# PiZeroAudioI2S.net
KiCad netlist of a schematic drawn in EAGLE
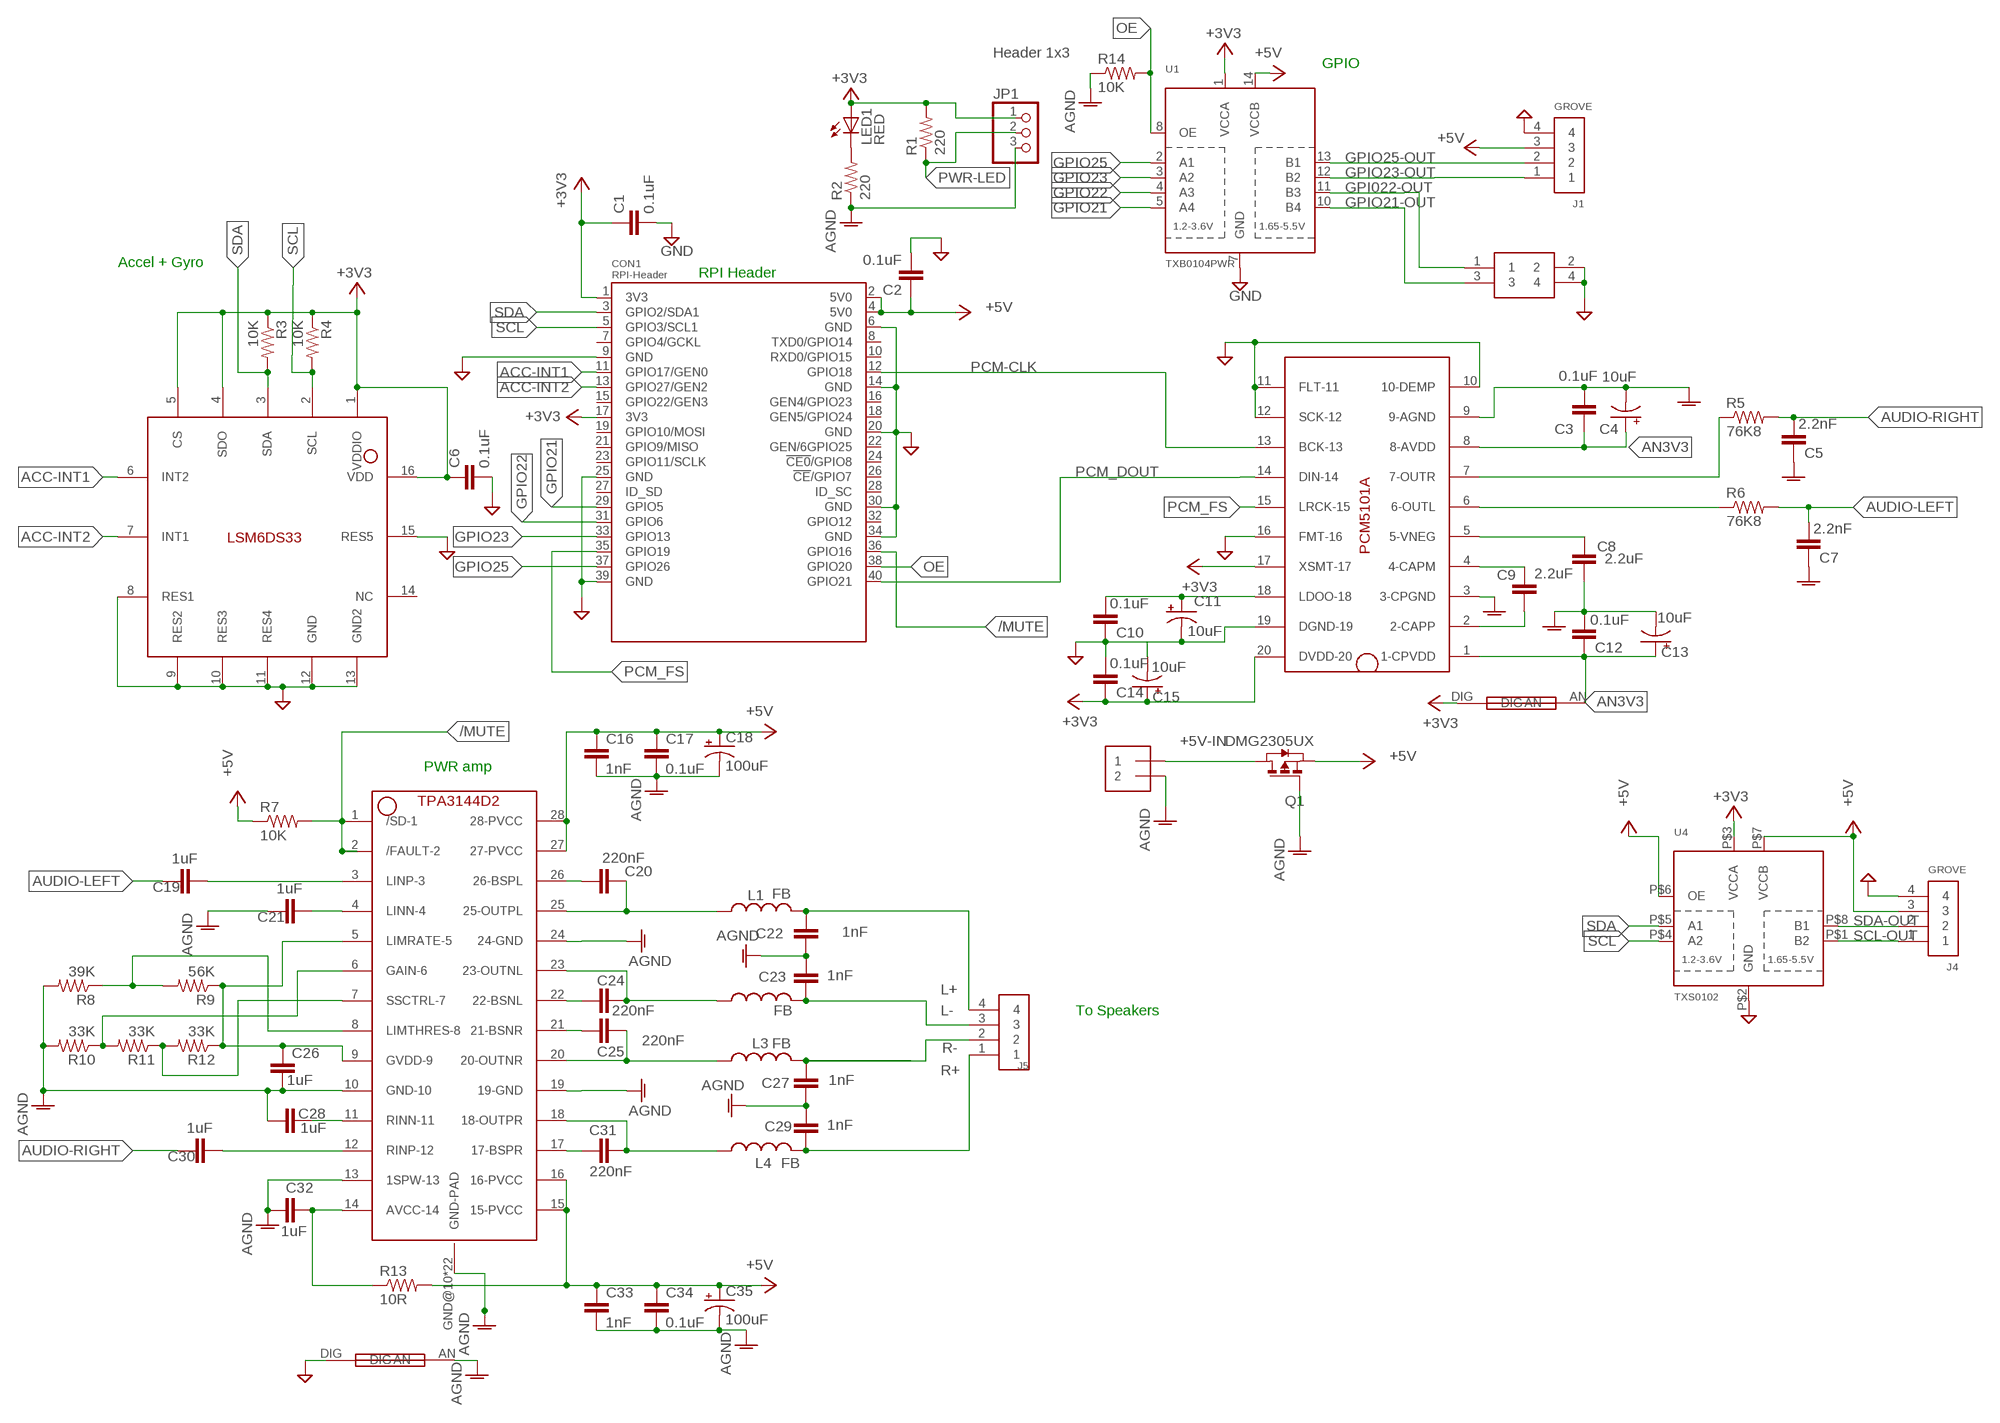
[diagram p0: schematic, sheet 1]

(export (version "E")
  (design (tool "Eeschema 10.0.6"))
  (components
    (comp (ref "C1")
      (value "0.1uF")
      (footprint "eagle-import:C0603")
      (libsource (lib "eagle-import") (part "C-EUC0603"))
    )
    (comp (ref "C2")
      (value "0.1uF")
      (footprint "eagle-import:C0603")
      (libsource (lib "eagle-import") (part "C-EUC0603"))
    )
    (comp (ref "C3")
      (value "0.1uF")
      (footprint "eagle-import:C0603")
      (libsource (lib "eagle-import") (part "C-EUC0603"))
    )
    (comp (ref "C4")
      (value "10uF")
      (footprint "eagle-import:EIA3216")
      (fields (field (name "MF") "AVX") (field (name "MPN") "F931C106MAA"))
      (libsource (lib "eagle-import") (part "CAP-POLARISED1206-POLAR"))
    )
    (comp (ref "C5")
      (value "2.2nF")
      (footprint "eagle-import:C0603")
      (fields (field (name "MF") "WALSIN") (field (name "MPN") "0603B222K500CT"))
      (libsource (lib "eagle-import") (part "C-EUC0603"))
    )
    (comp (ref "C6")
      (value "0.1uF")
      (footprint "eagle-import:C0603")
      (libsource (lib "eagle-import") (part "C-EUC0603"))
    )
    (comp (ref "C7")
      (value "2.2nF")
      (footprint "eagle-import:C0603")
      (fields (field (name "MF") "WALSIN") (field (name "MPN") "0603B222K500CT"))
      (libsource (lib "eagle-import") (part "C-EUC0603"))
    )
    (comp (ref "C8")
      (value "2.2uF")
      (footprint "eagle-import:C0603")
      (fields (field (name "MF") "KEMET") (field (name "MPN") "C0603C225K8PACTU"))
      (libsource (lib "eagle-import") (part "C-EUC0603"))
    )
    (comp (ref "C9")
      (value "2.2uF")
      (footprint "eagle-import:C0603")
      (fields (field (name "MF") "KEMET") (field (name "MPN") "C0603C225K8PACTU"))
      (libsource (lib "eagle-import") (part "C-EUC0603"))
    )
    (comp (ref "C10")
      (value "0.1uF")
      (footprint "eagle-import:C0603")
      (libsource (lib "eagle-import") (part "C-EUC0603"))
    )
    (comp (ref "C11")
      (value "10uF")
      (footprint "eagle-import:EIA3216")
      (fields (field (name "MF") "AVX") (field (name "MPN") "F931C106MAA"))
      (libsource (lib "eagle-import") (part "CAP-POLARISED1206-POLAR"))
    )
    (comp (ref "C12")
      (value "0.1uF")
      (footprint "eagle-import:C0603")
      (libsource (lib "eagle-import") (part "C-EUC0603"))
    )
    (comp (ref "C13")
      (value "10uF")
      (footprint "eagle-import:EIA3216")
      (fields (field (name "MF") "AVX") (field (name "MPN") "F931C106MAA"))
      (libsource (lib "eagle-import") (part "CAP-POLARISED1206-POLAR"))
    )
    (comp (ref "C14")
      (value "0.1uF")
      (footprint "eagle-import:C0603")
      (libsource (lib "eagle-import") (part "C-EUC0603"))
    )
    (comp (ref "C15")
      (value "10uF")
      (footprint "eagle-import:EIA3216")
      (fields (field (name "MF") "AVX") (field (name "MPN") "F931C106MAA"))
      (libsource (lib "eagle-import") (part "CAP-POLARISED1206-POLAR"))
    )
    (comp (ref "C16")
      (value "1nF")
      (footprint "eagle-import:C0603")
      (fields (field (name "MF") "AVX") (field (name "MPN") "06035C102KAT2A"))
      (libsource (lib "eagle-import") (part "C-EUC0603"))
    )
    (comp (ref "C17")
      (value "0.1uF")
      (footprint "eagle-import:C0603")
      (libsource (lib "eagle-import") (part "C-EUC0603"))
    )
    (comp (ref "C18")
      (value "100uF")
      (footprint "eagle-import:EIA3216")
      (fields (field (name "MF") "AVX") (field (name "MPN") "TLJA107M010R1400"))
      (libsource (lib "eagle-import") (part "CAP-POLARISED1206-POLAR"))
    )
    (comp (ref "C19")
      (value "1uF")
      (footprint "eagle-import:C0603")
      (libsource (lib "eagle-import") (part "C-EUC0603"))
    )
    (comp (ref "C20")
      (value "220nF")
      (footprint "eagle-import:C0603")
      (fields (field (name "MF") "TAIYO YUDEN") (field (name "MPN") "EMK107B7224KA-T"))
      (libsource (lib "eagle-import") (part "C-EUC0603"))
    )
    (comp (ref "C21")
      (value "1uF")
      (footprint "eagle-import:C0603")
      (libsource (lib "eagle-import") (part "C-EUC0603"))
    )
    (comp (ref "C22")
      (value "1nF")
      (footprint "eagle-import:C0603")
      (fields (field (name "MF") "AVX") (field (name "MPN") "06035C102KAT2A"))
      (libsource (lib "eagle-import") (part "C-EUC0603"))
    )
    (comp (ref "C23")
      (value "1nF")
      (footprint "eagle-import:C0603")
      (fields (field (name "MF") "AVX") (field (name "MPN") "06035C102KAT2A"))
      (libsource (lib "eagle-import") (part "C-EUC0603"))
    )
    (comp (ref "C24")
      (value "220nF")
      (footprint "eagle-import:C0603")
      (fields (field (name "MF") "TAIYO YUDEN") (field (name "MPN") "EMK107B7224KA-T"))
      (libsource (lib "eagle-import") (part "C-EUC0603"))
    )
    (comp (ref "C25")
      (value "220nF")
      (footprint "eagle-import:C0603")
      (fields (field (name "MF") "TAIYO YUDEN") (field (name "MPN") "EMK107B7224KA-T"))
      (libsource (lib "eagle-import") (part "C-EUC0603"))
    )
    (comp (ref "C26")
      (value "1uF")
      (footprint "eagle-import:C0603")
      (libsource (lib "eagle-import") (part "C-EUC0603"))
    )
    (comp (ref "C27")
      (value "1nF")
      (footprint "eagle-import:C0603")
      (fields (field (name "MF") "AVX") (field (name "MPN") "06035C102KAT2A"))
      (libsource (lib "eagle-import") (part "C-EUC0603"))
    )
    (comp (ref "C28")
      (value "1uF")
      (footprint "eagle-import:C0603")
      (libsource (lib "eagle-import") (part "C-EUC0603"))
    )
    (comp (ref "C29")
      (value "1nF")
      (footprint "eagle-import:C0603")
      (fields (field (name "MF") "AVX") (field (name "MPN") "06035C102KAT2A"))
      (libsource (lib "eagle-import") (part "C-EUC0603"))
    )
    (comp (ref "C30")
      (value "1uF")
      (footprint "eagle-import:C0603")
      (libsource (lib "eagle-import") (part "C-EUC0603"))
    )
    (comp (ref "C31")
      (value "220nF")
      (footprint "eagle-import:C0603")
      (fields (field (name "MF") "TAIYO YUDEN") (field (name "MPN") "EMK107B7224KA-T"))
      (libsource (lib "eagle-import") (part "C-EUC0603"))
    )
    (comp (ref "C32")
      (value "1uF")
      (footprint "eagle-import:C0603")
      (libsource (lib "eagle-import") (part "C-EUC0603"))
    )
    (comp (ref "C33")
      (value "1nF")
      (footprint "eagle-import:C0603")
      (fields (field (name "MF") "AVX") (field (name "MPN") "06035C102KAT2A"))
      (libsource (lib "eagle-import") (part "C-EUC0603"))
    )
    (comp (ref "C34")
      (value "0.1uF")
      (footprint "eagle-import:C0603")
      (libsource (lib "eagle-import") (part "C-EUC0603"))
    )
    (comp (ref "C35")
      (value "100uF")
      (footprint "eagle-import:EIA3216")
      (fields (field (name "MF") "AVX") (field (name "MPN") "TLJA107M010R1400"))
      (libsource (lib "eagle-import") (part "CAP-POLARISED1206-POLAR"))
    )
    (comp (ref "CON1")
      (value "RPI-Header")
      (footprint "eagle-import:RASPBERRYPI_BASTELSTUBE_V13_RASPI_BOARD_B+_FULL")
      (libsource (lib "eagle-import") (part "RPI-ZERO"))
    )
    (comp (ref "J1")
      (value "GROVE")
      (footprint "eagle-import:JST-PH4")
      (libsource (lib "eagle-import") (part "GROVE"))
    )
    (comp (ref "J2")
      (value "2X2HEADER")
      (footprint "eagle-import:2X2")
      (libsource (lib "eagle-import") (part "2X2HEADER"))
    )
    (comp (ref "J3")
      (value "2X1-LOCKING")
      (footprint "eagle-import:22-23-2021")
      (fields (field (name "MF") "MOLEX") (field (name "MPN") "22-23-2021"))
      (libsource (lib "eagle-import") (part "2X1-LOCKING"))
    )
    (comp (ref "J4")
      (value "GROVE")
      (footprint "eagle-import:JST-PH4")
      (libsource (lib "eagle-import") (part "GROVE"))
    )
    (comp (ref "J5")
      (value "4X1-LOCKING")
      (footprint "eagle-import:22-23-2041")
      (fields (field (name "MF") "MOLEX") (field (name "MPN") "22-23-2041"))
      (libsource (lib "eagle-import") (part "4X1-LOCKING"))
    )
    (comp (ref "JP1")
      (value "Header 1x3")
      (footprint "eagle-import:1X03")
      (libsource (lib "eagle-import") (part "PINHD-1X3"))
    )
    (comp (ref "L1")
      (value "FB")
      (footprint "eagle-import:L0806")
      (libsource (lib "eagle-import") (part "NFZ2MSML0806"))
    )
    (comp (ref "L2")
      (value "FB")
      (footprint "eagle-import:L0806")
      (libsource (lib "eagle-import") (part "NFZ2MSML0806"))
    )
    (comp (ref "L3")
      (value "FB")
      (footprint "eagle-import:L0806")
      (libsource (lib "eagle-import") (part "NFZ2MSML0806"))
    )
    (comp (ref "L4")
      (value "FB")
      (footprint "eagle-import:L0806")
      (libsource (lib "eagle-import") (part "NFZ2MSML0806"))
    )
    (comp (ref "LED1")
      (value "RED")
      (footprint "eagle-import:CHIP-LED0805")
      (libsource (lib "eagle-import") (part "LEDCHIP-LED0805"))
    )
    (comp (ref "Q1")
      (value "DMG2305UX")
      (footprint "eagle-import:SOT23")
      (fields (field (name "MF") "DIODES INC.") (field (name "MPN") "DMG2305UX-7"))
      (libsource (lib "eagle-import") (part "DMG2305UX"))
    )
    (comp (ref "R1")
      (value "220")
      (footprint "eagle-import:R0603")
      (libsource (lib "eagle-import") (part "R-US_R0603"))
    )
    (comp (ref "R2")
      (value "220")
      (footprint "eagle-import:R0603")
      (libsource (lib "eagle-import") (part "R-US_R0603"))
    )
    (comp (ref "R3")
      (value "10K")
      (footprint "eagle-import:R0603")
      (fields (field (name "MF") "YAGEO") (field (name "MPN") "RC0603FR-0710KL"))
      (libsource (lib "eagle-import") (part "R-US_R0603"))
    )
    (comp (ref "R4")
      (value "10K")
      (footprint "eagle-import:R0603")
      (fields (field (name "MF") "YAGEO") (field (name "MPN") "RC0603FR-0710KL"))
      (libsource (lib "eagle-import") (part "R-US_R0603"))
    )
    (comp (ref "R5")
      (value "76K8")
      (footprint "eagle-import:R0603")
      (fields (field (name "MF") "PANASONIC ELECTRONIC COMPONENTS") (field (name "MPN") "RMCF0603FT76K8"))
      (libsource (lib "eagle-import") (part "R-US_R0603"))
    )
    (comp (ref "R6")
      (value "76K8")
      (footprint "eagle-import:R0603")
      (fields (field (name "MF") "PANASONIC ELECTRONIC COMPONENTS") (field (name "MPN") "RMCF0603FT76K8"))
      (libsource (lib "eagle-import") (part "R-US_R0603"))
    )
    (comp (ref "R7")
      (value "10K")
      (footprint "eagle-import:R0603")
      (fields (field (name "MF") "YAGEO") (field (name "MPN") "RC0603FR-0710KL"))
      (libsource (lib "eagle-import") (part "R-US_R0603"))
    )
    (comp (ref "R8")
      (value "39K")
      (footprint "eagle-import:R0603")
      (fields (field (name "MF") "YAGEO") (field (name "MPN") "RC0603FR-0739KL"))
      (libsource (lib "eagle-import") (part "R-US_R0603"))
    )
    (comp (ref "R9")
      (value "56K")
      (footprint "eagle-import:R0603")
      (fields (field (name "MF") "VISHAY") (field (name "MPN") "CRCW060356K0FKEA."))
      (libsource (lib "eagle-import") (part "R-US_R0603"))
    )
    (comp (ref "R10")
      (value "33K")
      (footprint "eagle-import:R0603")
      (fields (field (name "MF") "MULTICOMP") (field (name "MPN") "MCMR06X3302FTL"))
      (libsource (lib "eagle-import") (part "R-US_R0603"))
    )
    (comp (ref "R11")
      (value "33K")
      (footprint "eagle-import:R0603")
      (fields (field (name "MF") "MULTICOMP") (field (name "MPN") "MCMR06X3302FTL"))
      (libsource (lib "eagle-import") (part "R-US_R0603"))
    )
    (comp (ref "R12")
      (value "33K")
      (footprint "eagle-import:R0603")
      (fields (field (name "MF") "MULTICOMP") (field (name "MPN") "MCMR06X3302FTL"))
      (libsource (lib "eagle-import") (part "R-US_R0603"))
    )
    (comp (ref "R13")
      (value "10R")
      (footprint "eagle-import:R0603")
      (libsource (lib "eagle-import") (part "R-US_R0603"))
    )
    (comp (ref "R14")
      (value "10K")
      (footprint "eagle-import:R0603")
      (fields (field (name "MF") "YAGEO") (field (name "MPN") "RC0603FR-0710KL"))
      (libsource (lib "eagle-import") (part "R-US_R0603"))
    )
    (comp (ref "SH1")
      (value "SHORT")
      (footprint "eagle-import:SHORT")
      (libsource (lib "eagle-import") (part "SHORT"))
    )
    (comp (ref "SH2")
      (value "SHORT")
      (footprint "eagle-import:SHORT")
      (libsource (lib "eagle-import") (part "SHORT"))
    )
    (comp (ref "U1")
      (value "TXB0104PWR")
      (footprint "eagle-import:TSSOP14")
      (fields (field (name "MF") "TEXAS INSTRUMENTS"))
      (libsource (lib "eagle-import") (part "TXB0104PWR"))
    )
    (comp (ref "U2")
      (value "LSM6DS33")
      (footprint "eagle-import:LGA-16-3X3")
      (fields (field (name "MF") "STMICROELECTRONICS") (field (name "MPN") "LSM6DS33TR"))
      (libsource (lib "eagle-import") (part "LSM6DS33LGA-16-3X3"))
    )
    (comp (ref "U3")
      (value "PCM5101A")
      (footprint "eagle-import:TSSOP20-0.65-6.5X4.4MM")
      (fields (field (name "MF") "TEXAS INSTRUMENTS") (field (name "MPN") "PCM5101AQPWRQ1"))
      (libsource (lib "eagle-import") (part "PCM5101A"))
    )
    (comp (ref "U4")
      (value "TXS0102")
      (footprint "eagle-import:VFSOP-8")
      (libsource (lib "eagle-import") (part "TXS0102"))
    )
    (comp (ref "U5")
      (value "TPA3144D2PWPR")
      (footprint "eagle-import:HTSSOP28")
      (libsource (lib "eagle-import") (part "TPA3144D2PWPR"))
    )
  )
  (nets
    (net (code "1") (name "+3V3") (class "Default")
      (node (ref "C1") (pin "1") (pinfunction "1_1") (pintype "passive"))
      (node (ref "C14") (pin "2") (pinfunction "2_2") (pintype "passive"))
      (node (ref "C15") (pin "+") (pinfunction "+_+") (pintype "passive"))
      (node (ref "C6") (pin "1") (pinfunction "1_1") (pintype "passive"))
      (node (ref "CON1") (pin "1") (pinfunction "3V3_1") (pintype "power_in"))
      (node (ref "CON1") (pin "17") (pinfunction "3V3_17") (pintype "power_in"))
      (node (ref "JP1") (pin "1") (pinfunction "1_1") (pintype "passive"))
      (node (ref "LED1") (pin "A") (pinfunction "A_A") (pintype "passive"))
      (node (ref "R1") (pin "2") (pinfunction "2_2") (pintype "passive"))
      (node (ref "R3") (pin "1") (pinfunction "1_1") (pintype "passive"))
      (node (ref "R4") (pin "1") (pinfunction "1_1") (pintype "passive"))
      (node (ref "SH1") (pin "DIG") (pinfunction "DIG_DIG") (pintype "bidirectional"))
      (node (ref "U1") (pin "1") (pinfunction "VCCA_1") (pintype "bidirectional"))
      (node (ref "U2") (pin "1") (pinfunction "VDDIO_1") (pintype "bidirectional"))
      (node (ref "U2") (pin "16") (pinfunction "VDD_16") (pintype "bidirectional"))
      (node (ref "U2") (pin "4") (pinfunction "SDO_4") (pintype "bidirectional"))
      (node (ref "U2") (pin "5") (pinfunction "CS_5") (pintype "bidirectional"))
      (node (ref "U3") (pin "17") (pinfunction "XSMT-17_17") (pintype "bidirectional"))
      (node (ref "U3") (pin "20") (pinfunction "DVDD-20_20") (pintype "bidirectional"))
      (node (ref "U4") (pin "P$3") (pinfunction "VCCA_P$3") (pintype "bidirectional"))
    )
    (net (code "2") (name "+5V") (class "Default")
      (node (ref "C16") (pin "1") (pinfunction "1_1") (pintype "passive"))
      (node (ref "C17") (pin "1") (pinfunction "1_1") (pintype "passive"))
      (node (ref "C18") (pin "+") (pinfunction "+_+") (pintype "passive"))
      (node (ref "C2") (pin "1") (pinfunction "1_1") (pintype "passive"))
      (node (ref "C33") (pin "1") (pinfunction "1_1") (pintype "passive"))
      (node (ref "C34") (pin "1") (pinfunction "1_1") (pintype "passive"))
      (node (ref "C35") (pin "+") (pinfunction "+_+") (pintype "passive"))
      (node (ref "CON1") (pin "2") (pinfunction "5V0_2") (pintype "power_in"))
      (node (ref "CON1") (pin "4") (pinfunction "5V0_4") (pintype "power_in"))
      (node (ref "J1") (pin "3") (pinfunction "3_3") (pintype "bidirectional"))
      (node (ref "J4") (pin "3") (pinfunction "3_3") (pintype "bidirectional"))
      (node (ref "Q1") (pin "S") (pinfunction "S_S") (pintype "passive"))
      (node (ref "R13") (pin "2") (pinfunction "2_2") (pintype "passive"))
      (node (ref "R7") (pin "1") (pinfunction "1_1") (pintype "passive"))
      (node (ref "U1") (pin "14") (pinfunction "VCCB_14") (pintype "bidirectional"))
      (node (ref "U4") (pin "P$6") (pinfunction "OE_P$6") (pintype "bidirectional"))
      (node (ref "U4") (pin "P$7") (pinfunction "VCCB_P$7") (pintype "bidirectional"))
      (node (ref "U5") (pin "15") (pinfunction "15-PVCC_15") (pintype "bidirectional"))
      (node (ref "U5") (pin "16") (pinfunction "16-PVCC_16") (pintype "bidirectional"))
      (node (ref "U5") (pin "27") (pinfunction "27-PVCC_27") (pintype "bidirectional"))
      (node (ref "U5") (pin "28") (pinfunction "28-PVCC_28") (pintype "bidirectional"))
    )
    (net (code "3") (name "/+5V-IN") (class "Default")
      (node (ref "J3") (pin "1") (pinfunction "1_1") (pintype "passive"))
      (node (ref "Q1") (pin "D") (pinfunction "D_D") (pintype "passive"))
    )
    (net (code "4") (name "/GPI022-OUT") (class "Default")
      (node (ref "J2") (pin "1") (pinfunction "1_1") (pintype "bidirectional"))
      (node (ref "U1") (pin "11") (pinfunction "B3_11") (pintype "bidirectional"))
    )
    (net (code "5") (name "/GPIO21-OUT") (class "Default")
      (node (ref "J2") (pin "3") (pinfunction "3_3") (pintype "bidirectional"))
      (node (ref "U1") (pin "10") (pinfunction "B4_10") (pintype "bidirectional"))
    )
    (net (code "6") (name "/GPIO23-OUT") (class "Default")
      (node (ref "J1") (pin "1") (pinfunction "1_1") (pintype "bidirectional"))
      (node (ref "U1") (pin "12") (pinfunction "B2_12") (pintype "bidirectional"))
    )
    (net (code "7") (name "/GPIO25-OUT") (class "Default")
      (node (ref "J1") (pin "2") (pinfunction "2_2") (pintype "bidirectional"))
      (node (ref "U1") (pin "13") (pinfunction "B1_13") (pintype "bidirectional"))
    )
    (net (code "8") (name "/L+") (class "Default")
      (node (ref "C22") (pin "1") (pinfunction "1_1") (pintype "passive"))
      (node (ref "J5") (pin "4") (pinfunction "4_4") (pintype "bidirectional"))
      (node (ref "L1") (pin "2") (pinfunction "2_2") (pintype "passive"))
    )
    (net (code "9") (name "/L-") (class "Default")
      (node (ref "C23") (pin "2") (pinfunction "2_2") (pintype "passive"))
      (node (ref "J5") (pin "3") (pinfunction "3_3") (pintype "bidirectional"))
      (node (ref "L2") (pin "2") (pinfunction "2_2") (pintype "passive"))
    )
    (net (code "10") (name "/PCM-CLK") (class "Default")
      (node (ref "CON1") (pin "12") (pinfunction "GPIO18_12") (pintype "bidirectional"))
      (node (ref "U3") (pin "13") (pinfunction "BCK-13_13") (pintype "bidirectional"))
    )
    (net (code "11") (name "/PCM_DOUT") (class "Default")
      (node (ref "CON1") (pin "40") (pinfunction "GPIO21_40") (pintype "bidirectional"))
      (node (ref "U3") (pin "14") (pinfunction "DIN-14_14") (pintype "bidirectional"))
    )
    (net (code "12") (name "/R+") (class "Default")
      (node (ref "C29") (pin "2") (pinfunction "2_2") (pintype "passive"))
      (node (ref "J5") (pin "1") (pinfunction "1_1") (pintype "bidirectional"))
      (node (ref "L4") (pin "2") (pinfunction "2_2") (pintype "passive"))
    )
    (net (code "13") (name "/R-") (class "Default")
      (node (ref "C27") (pin "1") (pinfunction "1_1") (pintype "passive"))
      (node (ref "J5") (pin "2") (pinfunction "2_2") (pintype "bidirectional"))
      (node (ref "L3") (pin "2") (pinfunction "2_2") (pintype "passive"))
    )
    (net (code "14") (name "/SCL-OUT") (class "Default")
      (node (ref "J4") (pin "1") (pinfunction "1_1") (pintype "bidirectional"))
      (node (ref "U4") (pin "P$1") (pinfunction "B2_P$1") (pintype "bidirectional"))
    )
    (net (code "15") (name "/SDA-OUT") (class "Default")
      (node (ref "J4") (pin "2") (pinfunction "2_2") (pintype "bidirectional"))
      (node (ref "U4") (pin "P$8") (pinfunction "B1_P$8") (pintype "bidirectional"))
    )
    (net (code "16") (name "ACC-INT1") (class "Default")
      (node (ref "CON1") (pin "11") (pinfunction "GPIO17/GEN0_11") (pintype "bidirectional"))
      (node (ref "U2") (pin "6") (pinfunction "INT2_6") (pintype "bidirectional"))
    )
    (net (code "17") (name "ACC-INT2") (class "Default")
      (node (ref "CON1") (pin "13") (pinfunction "GPIO27/GEN2_13") (pintype "bidirectional"))
      (node (ref "U2") (pin "7") (pinfunction "INT1_7") (pintype "bidirectional"))
    )
    (net (code "18") (name "AGND") (class "Default")
      (node (ref "C12") (pin "1") (pinfunction "1_1") (pintype "passive"))
      (node (ref "C13") (pin "-") (pinfunction "-_-") (pintype "passive"))
      (node (ref "C16") (pin "2") (pinfunction "2_2") (pintype "passive"))
      (node (ref "C17") (pin "2") (pinfunction "2_2") (pintype "passive"))
      (node (ref "C18") (pin "-") (pinfunction "-_-") (pintype "passive"))
      (node (ref "C21") (pin "2") (pinfunction "2_2") (pintype "passive"))
      (node (ref "C22") (pin "2") (pinfunction "2_2") (pintype "passive"))
      (node (ref "C23") (pin "1") (pinfunction "1_1") (pintype "passive"))
      (node (ref "C26") (pin "2") (pinfunction "2_2") (pintype "passive"))
      (node (ref "C27") (pin "2") (pinfunction "2_2") (pintype "passive"))
      (node (ref "C28") (pin "2") (pinfunction "2_2") (pintype "passive"))
      (node (ref "C29") (pin "1") (pinfunction "1_1") (pintype "passive"))
      (node (ref "C3") (pin "1") (pinfunction "1_1") (pintype "passive"))
      (node (ref "C32") (pin "2") (pinfunction "2_2") (pintype "passive"))
      (node (ref "C33") (pin "2") (pinfunction "2_2") (pintype "passive"))
      (node (ref "C34") (pin "2") (pinfunction "2_2") (pintype "passive"))
      (node (ref "C35") (pin "-") (pinfunction "-_-") (pintype "passive"))
      (node (ref "C4") (pin "-") (pinfunction "-_-") (pintype "passive"))
      (node (ref "C5") (pin "2") (pinfunction "2_2") (pintype "passive"))
      (node (ref "C7") (pin "2") (pinfunction "2_2") (pintype "passive"))
      (node (ref "C8") (pin "2") (pinfunction "2_2") (pintype "passive"))
      (node (ref "J3") (pin "2") (pinfunction "2_2") (pintype "passive"))
      (node (ref "JP1") (pin "3") (pinfunction "3_3") (pintype "passive"))
      (node (ref "Q1") (pin "G") (pinfunction "G_G") (pintype "passive"))
      (node (ref "R10") (pin "2") (pinfunction "2_2") (pintype "passive"))
      (node (ref "R14") (pin "1") (pinfunction "1_1") (pintype "passive"))
      (node (ref "R2") (pin "1") (pinfunction "1_1") (pintype "passive"))
      (node (ref "R8") (pin "2") (pinfunction "2_2") (pintype "passive"))
      (node (ref "SH2") (pin "AN") (pinfunction "AN_AN") (pintype "bidirectional"))
      (node (ref "U3") (pin "3") (pinfunction "3-CPGND_3") (pintype "bidirectional"))
      (node (ref "U3") (pin "9") (pinfunction "9-AGND_9") (pintype "bidirectional"))
      (node (ref "U5") (pin "10") (pinfunction "GND-10_10") (pintype "bidirectional"))
      (node (ref "U5") (pin "13") (pinfunction "1SPW-13_13") (pintype "bidirectional"))
      (node (ref "U5") (pin "19") (pinfunction "19-GND_19") (pintype "bidirectional"))
      (node (ref "U5") (pin "24") (pinfunction "24-GND_24") (pintype "bidirectional"))
      (node (ref "U5") (pin "GND@10") (pinfunction "GND-PAD_GND@10") (pintype "bidirectional"))
      (node (ref "U5") (pin "GND@11") (pinfunction "GND-PAD_GND@11") (pintype "bidirectional"))
      (node (ref "U5") (pin "GND@12") (pinfunction "GND-PAD_GND@12") (pintype "bidirectional"))
      (node (ref "U5") (pin "GND@13") (pinfunction "GND-PAD_GND@13") (pintype "bidirectional"))
      (node (ref "U5") (pin "GND@14") (pinfunction "GND-PAD_GND@14") (pintype "bidirectional"))
      (node (ref "U5") (pin "GND@15") (pinfunction "GND-PAD_GND@15") (pintype "bidirectional"))
      (node (ref "U5") (pin "GND@16") (pinfunction "GND-PAD_GND@16") (pintype "bidirectional"))
      (node (ref "U5") (pin "GND@17") (pinfunction "GND-PAD_GND@17") (pintype "bidirectional"))
      (node (ref "U5") (pin "GND@18") (pinfunction "GND-PAD_GND@18") (pintype "bidirectional"))
      (node (ref "U5") (pin "GND@19") (pinfunction "GND-PAD_GND@19") (pintype "bidirectional"))
      (node (ref "U5") (pin "GND@20") (pinfunction "GND-PAD_GND@20") (pintype "bidirectional"))
      (node (ref "U5") (pin "GND@21") (pinfunction "GND-PAD_GND@21") (pintype "bidirectional"))
      (node (ref "U5") (pin "GND@22") (pinfunction "GND-PAD_GND@22") (pintype "bidirectional"))
      (node (ref "U5") (pin "GND@23") (pinfunction "GND-PAD_GND@23") (pintype "bidirectional"))
      (node (ref "U5") (pin "GND@24") (pinfunction "GND-PAD_GND@24") (pintype "bidirectional"))
      (node (ref "U5") (pin "GND@25") (pinfunction "GND-PAD_GND@25") (pintype "bidirectional"))
      (node (ref "U5") (pin "GND@26") (pinfunction "GND-PAD_GND@26") (pintype "bidirectional"))
      (node (ref "U5") (pin "GND@27") (pinfunction "GND-PAD_GND@27") (pintype "bidirectional"))
      (node (ref "U5") (pin "GND@28") (pinfunction "GND-PAD_GND@28") (pintype "bidirectional"))
      (node (ref "U5") (pin "GND@29") (pinfunction "GND-PAD_GND@29") (pintype "bidirectional"))
      (node (ref "U5") (pin "GND@30") (pinfunction "GND-PAD_GND@30") (pintype "bidirectional"))
      (node (ref "U5") (pin "GND@PAD") (pinfunction "GND-PAD_GND@PAD") (pintype "bidirectional"))
    )
    (net (code "19") (name "AN3V3") (class "Default")
      (node (ref "C12") (pin "2") (pinfunction "2_2") (pintype "passive"))
      (node (ref "C13") (pin "+") (pinfunction "+_+") (pintype "passive"))
      (node (ref "C3") (pin "2") (pinfunction "2_2") (pintype "passive"))
      (node (ref "C4") (pin "+") (pinfunction "+_+") (pintype "passive"))
      (node (ref "SH1") (pin "AN") (pinfunction "AN_AN") (pintype "bidirectional"))
      (node (ref "U3") (pin "1") (pinfunction "1-CPVDD_1") (pintype "bidirectional"))
      (node (ref "U3") (pin "8") (pinfunction "8-AVDD_8") (pintype "bidirectional"))
    )
    (net (code "20") (name "AUDIO-LEFT") (class "Default")
      (node (ref "C19") (pin "2") (pinfunction "2_2") (pintype "passive"))
      (node (ref "C7") (pin "1") (pinfunction "1_1") (pintype "passive"))
      (node (ref "R6") (pin "2") (pinfunction "2_2") (pintype "passive"))
    )
    (net (code "21") (name "AUDIO-RIGHT") (class "Default")
      (node (ref "C30") (pin "2") (pinfunction "2_2") (pintype "passive"))
      (node (ref "C5") (pin "1") (pinfunction "1_1") (pintype "passive"))
      (node (ref "R5") (pin "2") (pinfunction "2_2") (pintype "passive"))
    )
    (net (code "22") (name "GND") (class "Default")
      (node (ref "C1") (pin "2") (pinfunction "2_2") (pintype "passive"))
      (node (ref "C10") (pin "2") (pinfunction "2_2") (pintype "passive"))
      (node (ref "C11") (pin "-") (pinfunction "-_-") (pintype "passive"))
      (node (ref "C14") (pin "1") (pinfunction "1_1") (pintype "passive"))
      (node (ref "C15") (pin "-") (pinfunction "-_-") (pintype "passive"))
      (node (ref "C2") (pin "2") (pinfunction "2_2") (pintype "passive"))
      (node (ref "C6") (pin "2") (pinfunction "2_2") (pintype "passive"))
      (node (ref "CON1") (pin "14") (pinfunction "GND_14") (pintype "power_in"))
      (node (ref "CON1") (pin "20") (pinfunction "GND_20") (pintype "power_in"))
      (node (ref "CON1") (pin "25") (pinfunction "GND_25") (pintype "power_in"))
      (node (ref "CON1") (pin "30") (pinfunction "GND_30") (pintype "power_in"))
      (node (ref "CON1") (pin "34") (pinfunction "GND_34") (pintype "power_in"))
      (node (ref "CON1") (pin "39") (pinfunction "GND_39") (pintype "power_in"))
      (node (ref "CON1") (pin "6") (pinfunction "GND_6") (pintype "power_in"))
      (node (ref "CON1") (pin "9") (pinfunction "GND_9") (pintype "power_in"))
      (node (ref "J1") (pin "4") (pinfunction "4_4") (pintype "bidirectional"))
      (node (ref "J2") (pin "2") (pinfunction "2_2") (pintype "bidirectional"))
      (node (ref "J2") (pin "4") (pinfunction "4_4") (pintype "bidirectional"))
      (node (ref "J4") (pin "4") (pinfunction "4_4") (pintype "bidirectional"))
      (node (ref "SH2") (pin "DIG") (pinfunction "DIG_DIG") (pintype "bidirectional"))
      (node (ref "U1") (pin "7") (pinfunction "GND_7") (pintype "bidirectional"))
      (node (ref "U2") (pin "10") (pinfunction "RES3_10") (pintype "bidirectional"))
      (node (ref "U2") (pin "11") (pinfunction "RES4_11") (pintype "bidirectional"))
      (node (ref "U2") (pin "12") (pinfunction "GND_12") (pintype "bidirectional"))
      (node (ref "U2") (pin "13") (pinfunction "GND2_13") (pintype "bidirectional"))
      (node (ref "U2") (pin "15") (pinfunction "RES5_15") (pintype "bidirectional"))
      (node (ref "U2") (pin "8") (pinfunction "RES1_8") (pintype "bidirectional"))
      (node (ref "U2") (pin "9") (pinfunction "RES2_9") (pintype "bidirectional"))
      (node (ref "U3") (pin "10") (pinfunction "10-DEMP_10") (pintype "bidirectional"))
      (node (ref "U3") (pin "11") (pinfunction "FLT-11_11") (pintype "bidirectional"))
      (node (ref "U3") (pin "12") (pinfunction "SCK-12_12") (pintype "bidirectional"))
      (node (ref "U3") (pin "16") (pinfunction "FMT-16_16") (pintype "bidirectional"))
      (node (ref "U3") (pin "19") (pinfunction "DGND-19_19") (pintype "bidirectional"))
      (node (ref "U4") (pin "P$2") (pinfunction "GND_P$2") (pintype "bidirectional"))
    )
    (net (code "23") (name "GPIO21") (class "Default")
      (node (ref "CON1") (pin "29") (pinfunction "GPIO5_29") (pintype "bidirectional"))
      (node (ref "U1") (pin "5") (pinfunction "A4_5") (pintype "bidirectional"))
    )
    (net (code "24") (name "GPIO22") (class "Default")
      (node (ref "CON1") (pin "31") (pinfunction "GPIO6_31") (pintype "bidirectional"))
      (node (ref "U1") (pin "4") (pinfunction "A3_4") (pintype "bidirectional"))
    )
    (net (code "25") (name "GPIO23") (class "Default")
      (node (ref "CON1") (pin "33") (pinfunction "GPIO13_33") (pintype "bidirectional"))
      (node (ref "U1") (pin "3") (pinfunction "A2_3") (pintype "bidirectional"))
    )
    (net (code "26") (name "GPIO25") (class "Default")
      (node (ref "CON1") (pin "37") (pinfunction "GPIO26_37") (pintype "bidirectional"))
      (node (ref "U1") (pin "2") (pinfunction "A1_2") (pintype "bidirectional"))
    )
    (net (code "27") (name "Net-(LED1-PadC)") (class "Default")
      (node (ref "LED1") (pin "C") (pinfunction "C_C") (pintype "passive"))
      (node (ref "R2") (pin "2") (pinfunction "2_2") (pintype "passive"))
    )
    (net (code "28") (name "Net-(U3-2-CAPP)") (class "Default")
      (node (ref "C9") (pin "2") (pinfunction "2_2") (pintype "passive"))
      (node (ref "U3") (pin "2") (pinfunction "2-CAPP_2") (pintype "bidirectional"))
    )
    (net (code "29") (name "Net-(U3-4-CAPM)") (class "Default")
      (node (ref "C9") (pin "1") (pinfunction "1_1") (pintype "passive"))
      (node (ref "U3") (pin "4") (pinfunction "4-CAPM_4") (pintype "bidirectional"))
    )
    (net (code "30") (name "Net-(U3-5-VNEG)") (class "Default")
      (node (ref "C8") (pin "1") (pinfunction "1_1") (pintype "passive"))
      (node (ref "U3") (pin "5") (pinfunction "5-VNEG_5") (pintype "bidirectional"))
    )
    (net (code "31") (name "Net-(U3-6-OUTL)") (class "Default")
      (node (ref "R6") (pin "1") (pinfunction "1_1") (pintype "passive"))
      (node (ref "U3") (pin "6") (pinfunction "6-OUTL_6") (pintype "bidirectional"))
    )
    (net (code "32") (name "Net-(U3-7-OUTR)") (class "Default")
      (node (ref "R5") (pin "1") (pinfunction "1_1") (pintype "passive"))
      (node (ref "U3") (pin "7") (pinfunction "7-OUTR_7") (pintype "bidirectional"))
    )
    (net (code "33") (name "Net-(U3-LDOO-18)") (class "Default")
      (node (ref "C10") (pin "1") (pinfunction "1_1") (pintype "passive"))
      (node (ref "C11") (pin "+") (pinfunction "+_+") (pintype "passive"))
      (node (ref "U3") (pin "18") (pinfunction "LDOO-18_18") (pintype "bidirectional"))
    )
    (net (code "34") (name "Net-(U5-17-BSPR)") (class "Default")
      (node (ref "C31") (pin "2") (pinfunction "2_2") (pintype "passive"))
      (node (ref "U5") (pin "17") (pinfunction "17-BSPR_17") (pintype "bidirectional"))
    )
    (net (code "35") (name "Net-(U5-18-OUTPR)") (class "Default")
      (node (ref "C31") (pin "1") (pinfunction "1_1") (pintype "passive"))
      (node (ref "L4") (pin "1") (pinfunction "1_1") (pintype "passive"))
      (node (ref "U5") (pin "18") (pinfunction "18-OUTPR_18") (pintype "bidirectional"))
    )
    (net (code "36") (name "Net-(U5-20-OUTNR)") (class "Default")
      (node (ref "C25") (pin "1") (pinfunction "1_1") (pintype "passive"))
      (node (ref "L3") (pin "1") (pinfunction "1_1") (pintype "passive"))
      (node (ref "U5") (pin "20") (pinfunction "20-OUTNR_20") (pintype "bidirectional"))
    )
    (net (code "37") (name "Net-(U5-21-BSNR)") (class "Default")
      (node (ref "C25") (pin "2") (pinfunction "2_2") (pintype "passive"))
      (node (ref "U5") (pin "21") (pinfunction "21-BSNR_21") (pintype "bidirectional"))
    )
    (net (code "38") (name "Net-(U5-22-BSNL)") (class "Default")
      (node (ref "C24") (pin "2") (pinfunction "2_2") (pintype "passive"))
      (node (ref "U5") (pin "22") (pinfunction "22-BSNL_22") (pintype "bidirectional"))
    )
    (net (code "39") (name "Net-(U5-23-OUTNL)") (class "Default")
      (node (ref "C24") (pin "1") (pinfunction "1_1") (pintype "passive"))
      (node (ref "L2") (pin "1") (pinfunction "1_1") (pintype "passive"))
      (node (ref "U5") (pin "23") (pinfunction "23-OUTNL_23") (pintype "bidirectional"))
    )
    (net (code "40") (name "Net-(U5-25-OUTPL)") (class "Default")
      (node (ref "C20") (pin "1") (pinfunction "1_1") (pintype "passive"))
      (node (ref "L1") (pin "1") (pinfunction "1_1") (pintype "passive"))
      (node (ref "U5") (pin "25") (pinfunction "25-OUTPL_25") (pintype "bidirectional"))
    )
    (net (code "41") (name "Net-(U5-26-BSPL)") (class "Default")
      (node (ref "C20") (pin "2") (pinfunction "2_2") (pintype "passive"))
      (node (ref "U5") (pin "26") (pinfunction "26-BSPL_26") (pintype "bidirectional"))
    )
    (net (code "42") (name "Net-(U5-AVCC-14)") (class "Default")
      (node (ref "C32") (pin "1") (pinfunction "1_1") (pintype "passive"))
      (node (ref "R13") (pin "1") (pinfunction "1_1") (pintype "passive"))
      (node (ref "U5") (pin "14") (pinfunction "AVCC-14_14") (pintype "bidirectional"))
    )
    (net (code "43") (name "Net-(U5-GAIN-6)") (class "Default")
      (node (ref "R10") (pin "1") (pinfunction "1_1") (pintype "passive"))
      (node (ref "R11") (pin "2") (pinfunction "2_2") (pintype "passive"))
      (node (ref "U5") (pin "6") (pinfunction "GAIN-6_6") (pintype "bidirectional"))
    )
    (net (code "44") (name "Net-(U5-GVDD-9)") (class "Default")
      (node (ref "C26") (pin "1") (pinfunction "1_1") (pintype "passive"))
      (node (ref "R12") (pin "1") (pinfunction "1_1") (pintype "passive"))
      (node (ref "R9") (pin "1") (pinfunction "1_1") (pintype "passive"))
      (node (ref "U5") (pin "5") (pinfunction "LIMRATE-5_5") (pintype "bidirectional"))
      (node (ref "U5") (pin "9") (pinfunction "GVDD-9_9") (pintype "bidirectional"))
    )
    (net (code "45") (name "Net-(U5-LIMTHRES-8)") (class "Default")
      (node (ref "R8") (pin "1") (pinfunction "1_1") (pintype "passive"))
      (node (ref "R9") (pin "2") (pinfunction "2_2") (pintype "passive"))
      (node (ref "U5") (pin "8") (pinfunction "LIMTHRES-8_8") (pintype "bidirectional"))
    )
    (net (code "46") (name "Net-(U5-LINN-4)") (class "Default")
      (node (ref "C21") (pin "1") (pinfunction "1_1") (pintype "passive"))
      (node (ref "U5") (pin "4") (pinfunction "LINN-4_4") (pintype "bidirectional"))
    )
    (net (code "47") (name "Net-(U5-LINP-3)") (class "Default")
      (node (ref "C19") (pin "1") (pinfunction "1_1") (pintype "passive"))
      (node (ref "U5") (pin "3") (pinfunction "LINP-3_3") (pintype "bidirectional"))
    )
    (net (code "48") (name "Net-(U5-RINN-11)") (class "Default")
      (node (ref "C28") (pin "1") (pinfunction "1_1") (pintype "passive"))
      (node (ref "U5") (pin "11") (pinfunction "RINN-11_11") (pintype "bidirectional"))
    )
    (net (code "49") (name "Net-(U5-RINP-12)") (class "Default")
      (node (ref "C30") (pin "1") (pinfunction "1_1") (pintype "passive"))
      (node (ref "U5") (pin "12") (pinfunction "RINP-12_12") (pintype "bidirectional"))
    )
    (net (code "50") (name "Net-(U5-SSCTRL-7)") (class "Default")
      (node (ref "R11") (pin "1") (pinfunction "1_1") (pintype "passive"))
      (node (ref "R12") (pin "2") (pinfunction "2_2") (pintype "passive"))
      (node (ref "U5") (pin "7") (pinfunction "SSCTRL-7_7") (pintype "bidirectional"))
    )
    (net (code "51") (name "OE") (class "Default")
      (node (ref "CON1") (pin "38") (pinfunction "GPIO20_38") (pintype "bidirectional"))
      (node (ref "R14") (pin "2") (pinfunction "2_2") (pintype "passive"))
      (node (ref "U1") (pin "8") (pinfunction "OE_8") (pintype "bidirectional"))
    )
    (net (code "52") (name "PCM_FS") (class "Default")
      (node (ref "CON1") (pin "35") (pinfunction "GPIO19_35") (pintype "bidirectional"))
      (node (ref "U3") (pin "15") (pinfunction "LRCK-15_15") (pintype "bidirectional"))
    )
    (net (code "53") (name "PWR-LED") (class "Default")
      (node (ref "JP1") (pin "2") (pinfunction "2_2") (pintype "passive"))
      (node (ref "R1") (pin "1") (pinfunction "1_1") (pintype "passive"))
    )
    (net (code "54") (name "SCL") (class "Default")
      (node (ref "CON1") (pin "5") (pinfunction "GPIO3/SCL1_5") (pintype "bidirectional"))
      (node (ref "R4") (pin "2") (pinfunction "2_2") (pintype "passive"))
      (node (ref "U2") (pin "2") (pinfunction "SCL_2") (pintype "bidirectional"))
      (node (ref "U4") (pin "P$4") (pinfunction "A2_P$4") (pintype "bidirectional"))
    )
    (net (code "55") (name "SDA") (class "Default")
      (node (ref "CON1") (pin "3") (pinfunction "GPIO2/SDA1_3") (pintype "bidirectional"))
      (node (ref "R3") (pin "2") (pinfunction "2_2") (pintype "passive"))
      (node (ref "U2") (pin "3") (pinfunction "SDA_3") (pintype "bidirectional"))
      (node (ref "U4") (pin "P$5") (pinfunction "A1_P$5") (pintype "bidirectional"))
    )
    (net (code "56") (name "unconnected-(CON1-GEN4{slash}GPIO23-Pad16)") (class "Default")
      (node (ref "CON1") (pin "16") (pinfunction "GEN4/GPIO23_16") (pintype "bidirectional"))
    )
    (net (code "57") (name "unconnected-(CON1-GEN5{slash}GPIO24-Pad18)") (class "Default")
      (node (ref "CON1") (pin "18") (pinfunction "GEN5/GPIO24_18") (pintype "bidirectional"))
    )
    (net (code "58") (name "unconnected-(CON1-GEN{slash}6GPIO25-Pad22)") (class "Default")
      (node (ref "CON1") (pin "22") (pinfunction "GEN/6GPIO25_22") (pintype "bidirectional"))
    )
    (net (code "59") (name "unconnected-(CON1-GPIO4{slash}GCKL-Pad7)") (class "Default")
      (node (ref "CON1") (pin "7") (pinfunction "GPIO4/GCKL_7") (pintype "bidirectional"))
    )
    (net (code "60") (name "unconnected-(CON1-GPIO9{slash}MISO-Pad21)") (class "Default")
      (node (ref "CON1") (pin "21") (pinfunction "GPIO9/MISO_21") (pintype "bidirectional"))
    )
    (net (code "61") (name "unconnected-(CON1-GPIO10{slash}MOSI-Pad19)") (class "Default")
      (node (ref "CON1") (pin "19") (pinfunction "GPIO10/MOSI_19") (pintype "bidirectional"))
    )
    (net (code "62") (name "unconnected-(CON1-GPIO11{slash}SCLK-Pad23)") (class "Default")
      (node (ref "CON1") (pin "23") (pinfunction "GPIO11/SCLK_23") (pintype "bidirectional"))
    )
    (net (code "63") (name "unconnected-(CON1-GPIO12-Pad32)") (class "Default")
      (node (ref "CON1") (pin "32") (pinfunction "GPIO12_32") (pintype "bidirectional"))
    )
    (net (code "64") (name "unconnected-(CON1-GPIO22{slash}GEN3-Pad15)") (class "Default")
      (node (ref "CON1") (pin "15") (pinfunction "GPIO22/GEN3_15") (pintype "bidirectional"))
    )
    (net (code "65") (name "unconnected-(CON1-ID_SC-Pad28)") (class "Default")
      (node (ref "CON1") (pin "28") (pinfunction "ID_SC_28") (pintype "bidirectional"))
    )
    (net (code "66") (name "unconnected-(CON1-ID_SD-Pad27)") (class "Default")
      (node (ref "CON1") (pin "27") (pinfunction "ID_SD_27") (pintype "bidirectional"))
    )
    (net (code "67") (name "unconnected-(CON1-RXD0{slash}GPIO15-Pad10)") (class "Default")
      (node (ref "CON1") (pin "10") (pinfunction "RXD0/GPIO15_10") (pintype "bidirectional"))
    )
    (net (code "68") (name "unconnected-(CON1-TXD0{slash}GPIO14-Pad8)") (class "Default")
      (node (ref "CON1") (pin "8") (pinfunction "TXD0/GPIO14_8") (pintype "bidirectional"))
    )
    (net (code "69") (name "unconnected-(CON1-~{CE0}{slash}GPIO8-Pad24)") (class "Default")
      (node (ref "CON1") (pin "24") (pinfunction "~{CE0}/GPIO8_24") (pintype "bidirectional"))
    )
    (net (code "70") (name "unconnected-(CON1-~{CE}{slash}GPIO7-Pad26)") (class "Default")
      (node (ref "CON1") (pin "26") (pinfunction "~{CE}/GPIO7_26") (pintype "bidirectional"))
    )
    (net (code "71") (name "unconnected-(U2-NC-Pad14)") (class "Default")
      (node (ref "U2") (pin "14") (pinfunction "NC_14") (pintype "bidirectional"))
    )
    (net (code "72") (name "{slash}MUTE") (class "Default")
      (node (ref "CON1") (pin "36") (pinfunction "GPIO16_36") (pintype "bidirectional"))
      (node (ref "R7") (pin "2") (pinfunction "2_2") (pintype "passive"))
      (node (ref "U5") (pin "1") (pinfunction "/SD-1_1") (pintype "bidirectional"))
      (node (ref "U5") (pin "2") (pinfunction "/FAULT-2_2") (pintype "bidirectional"))
    )
  )
)
